# disk.net
KiCad netlist of a schematic drawn in EAGLE
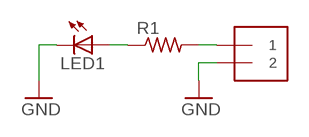
[diagram p0: schematic, sheet 1]

(export (version "E")
  (design (tool "Eeschema 10.0.6"))
  (components
    (comp (ref "J1")
      (value "1X2-3.5MM")
      (footprint "eagle-import:1X2-3.5MM")
      (libsource (lib "eagle-import") (part "1X2-3.5MM"))
    )
    (comp (ref "LED1")
      (value "LEDCHIPLED_0805")
      (footprint "eagle-import:CHIPLED_0805")
      (libsource (lib "eagle-import") (part "LEDCHIPLED_0805"))
    )
    (comp (ref "R1")
      (value "R-US_M0805")
      (footprint "eagle-import:M0805")
      (libsource (lib "eagle-import") (part "R-US_M0805"))
    )
  )
  (nets
    (net (code "1") (name "GND") (class "Default")
      (node (ref "J1") (pin "2") (pinfunction "2_2") (pintype "passive"))
      (node (ref "LED1") (pin "C") (pinfunction "C_C") (pintype "passive"))
    )
    (net (code "2") (name "Net-(J1-Pad1)") (class "Default")
      (node (ref "J1") (pin "1") (pinfunction "1_1") (pintype "passive"))
      (node (ref "R1") (pin "2") (pinfunction "2_2") (pintype "passive"))
    )
    (net (code "3") (name "Net-(LED1-PadA)") (class "Default")
      (node (ref "LED1") (pin "A") (pinfunction "A_A") (pintype "passive"))
      (node (ref "R1") (pin "1") (pinfunction "1_1") (pintype "passive"))
    )
  )
)
